# Serializer.net
KiCad netlist of a schematic drawn in Altium Designer
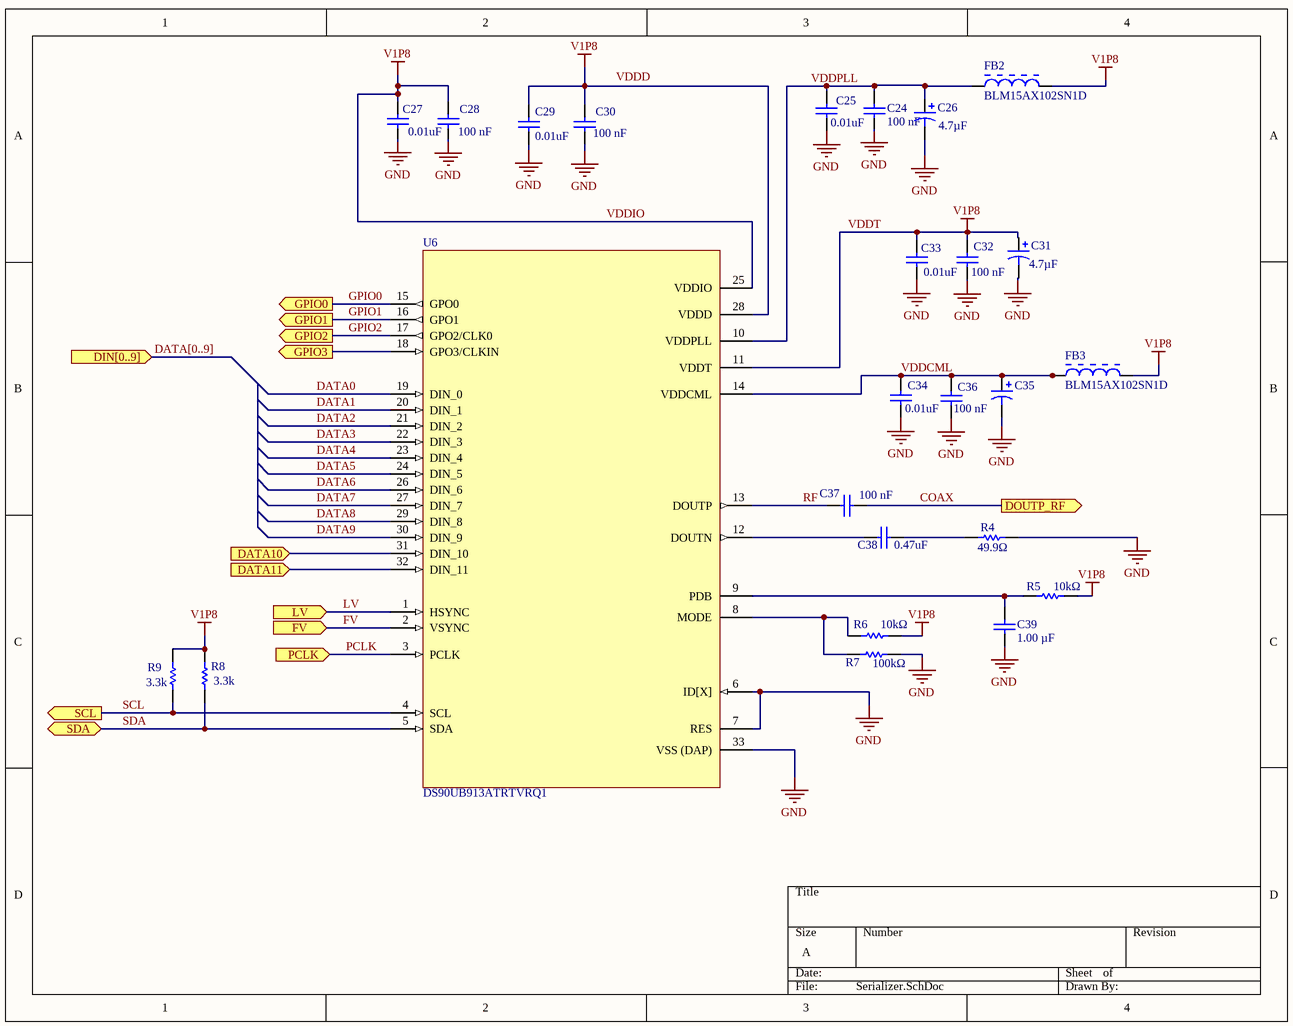
[diagram p0: Serializer.SchDoc]

(export (version "E")
  (design (tool "Eeschema 10.0.6"))
  (components
    (comp (ref "C24")
      (value "GRM033C71C104KE14D")
      (footprint "PCB-v6eq6etc9p7u7qdkgnno-1")
      (description "0.1 µF ±10% 16V Ceramic Capacitor X7S 0201 (0603 Metric)")
      (fields (field (name "CAPACITANCE") "100 nF"))
      (libsource (lib "Python_Imaging_1") (part "CMP-cc290632c88a13ee-3"))
    )
    (comp (ref "C25")
      (value "GRM033R71A103KA01D")
      (footprint "PCB-v6eq6etc9p7u7qdkgnno-1")
      (description "10000 pF ±10% 10V Ceramic Capacitor X7R 0201 (0603 Metric)")
      (fields (field (name "CAPACITANCE") "0.01uF"))
      (libsource (lib "Python_Imaging_1") (part "CMP-19299660-4"))
    )
    (comp (ref "C26")
      (value "F981A475MUALZT")
      (footprint "PCB-t0dwbiosd2m6unyihqym-1")
      (description "4.7 µF Molded Tantalum Capacitors 10 V 0402 (1005 Metric) -")
      (fields (field (name "CAPACITANCE") "4.7µF"))
      (libsource (lib "Python_Imaging_1") (part "SYM-b7737c8c1b6d68b4-1"))
    )
    (comp (ref "C27")
      (value "GRM033R71A103KA01D")
      (footprint "PCB-v6eq6etc9p7u7qdkgnno-1")
      (description "10000 pF ±10% 10V Ceramic Capacitor X7R 0201 (0603 Metric)")
      (fields (field (name "CAPACITANCE") "0.01uF"))
      (libsource (lib "Python_Imaging_1") (part "CMP-19299660-4"))
    )
    (comp (ref "C28")
      (value "GRM033C71C104KE14D")
      (footprint "PCB-v6eq6etc9p7u7qdkgnno-1")
      (description "0.1 µF ±10% 16V Ceramic Capacitor X7S 0201 (0603 Metric)")
      (fields (field (name "CAPACITANCE") "100 nF"))
      (libsource (lib "Python_Imaging_1") (part "CMP-cc290632c88a13ee-3"))
    )
    (comp (ref "C29")
      (value "GRM033R71A103KA01D")
      (footprint "PCB-v6eq6etc9p7u7qdkgnno-1")
      (description "10000 pF ±10% 10V Ceramic Capacitor X7R 0201 (0603 Metric)")
      (fields (field (name "CAPACITANCE") "0.01uF"))
      (libsource (lib "Python_Imaging_1") (part "CMP-19299660-4"))
    )
    (comp (ref "C30")
      (value "GRM033C71C104KE14D")
      (footprint "PCB-v6eq6etc9p7u7qdkgnno-1")
      (description "0.1 µF ±10% 16V Ceramic Capacitor X7S 0201 (0603 Metric)")
      (fields (field (name "CAPACITANCE") "100 nF"))
      (libsource (lib "Python_Imaging_1") (part "CMP-cc290632c88a13ee-3"))
    )
    (comp (ref "C31")
      (value "F981A475MUALZT")
      (footprint "PCB-t0dwbiosd2m6unyihqym-1")
      (description "4.7 µF Molded Tantalum Capacitors 10 V 0402 (1005 Metric) -")
      (fields (field (name "CAPACITANCE") "4.7µF"))
      (libsource (lib "Python_Imaging_1") (part "SYM-b7737c8c1b6d68b4-1"))
    )
    (comp (ref "C32")
      (value "GRM033C71C104KE14D")
      (footprint "PCB-v6eq6etc9p7u7qdkgnno-1")
      (description "0.1 µF ±10% 16V Ceramic Capacitor X7S 0201 (0603 Metric)")
      (fields (field (name "CAPACITANCE") "100 nF"))
      (libsource (lib "Python_Imaging_1") (part "CMP-cc290632c88a13ee-3"))
    )
    (comp (ref "C33")
      (value "GRM033R71A103KA01D")
      (footprint "PCB-v6eq6etc9p7u7qdkgnno-1")
      (description "10000 pF ±10% 10V Ceramic Capacitor X7R 0201 (0603 Metric)")
      (fields (field (name "CAPACITANCE") "0.01uF"))
      (libsource (lib "Python_Imaging_1") (part "CMP-19299660-4"))
    )
    (comp (ref "C34")
      (value "GRM033R71A103KA01D")
      (footprint "PCB-v6eq6etc9p7u7qdkgnno-1")
      (description "10000 pF ±10% 10V Ceramic Capacitor X7R 0201 (0603 Metric)")
      (fields (field (name "CAPACITANCE") "0.01uF"))
      (libsource (lib "Python_Imaging_1") (part "CMP-19299660-4"))
    )
    (comp (ref "C35")
      (value "F981A226MMALZT")
      (footprint "PCB-yxd74t6run51sg1ha7ug-1")
      (description "22 µF Molded Tantalum Capacitors 10 V 0603 (1608 Metric) 8Ohm @ 100kHz")
      (libsource (lib "Python_Imaging_1") (part "CMP-ed552659f9643292-2"))
    )
    (comp (ref "C36")
      (value "GRM033C71C104KE14D")
      (footprint "PCB-v6eq6etc9p7u7qdkgnno-1")
      (description "0.1 µF ±10% 16V Ceramic Capacitor X7S 0201 (0603 Metric)")
      (fields (field (name "CAPACITANCE") "100 nF"))
      (libsource (lib "Python_Imaging_1") (part "CMP-cc290632c88a13ee-3"))
    )
    (comp (ref "C37")
      (value "GRM033C71C104KE14D")
      (footprint "PCB-v6eq6etc9p7u7qdkgnno-1")
      (description "0.1 µF ±10% 16V Ceramic Capacitor X7S 0201 (0603 Metric)")
      (fields (field (name "CAPACITANCE") "100 nF"))
      (libsource (lib "Python_Imaging_1") (part "CMP-cc290632c88a13ee-3"))
    )
    (comp (ref "C38")
      (value "GRM033R60J473KE19D")
      (footprint "PCB-v6eq6etc9p7u7qdkgnno-1")
      (description "0.047 µF ±10% 6.3V Ceramic Capacitor X5R 0201 (0603 Metric)")
      (fields (field (name "CAPACITANCE") "0.47uF"))
      (libsource (lib "Python_Imaging_1") (part "CMP-131779-4"))
    )
    (comp (ref "C39")
      (value "GRM033R60J105MEA2D")
      (footprint "PCB-v6eq6etc9p7u7qdkgnno-1")
      (description "1 µF ±20% 6.3V Ceramic Capacitor X5R 0201 (0603 Metric)")
      (fields (field (name "CAPACITANCE") "1.00 µF"))
      (libsource (lib "Python_Imaging_1") (part "CMP-7dcab586fd61a20d-5"))
    )
    (comp (ref "FB2")
      (value "BLM15AX102SN1D")
      (footprint "MURA-BLM15-CHIP-2_V")
      (description "1 kOhms @ 100 MHz 1 - Ferrite Bead 0402 (1005 Metric) 350mA 490mOhm")
      (libsource (lib "Python_Imaging_1") (part "MURA-FB-2"))
    )
    (comp (ref "FB3")
      (value "BLM15AX102SN1D")
      (footprint "MURA-BLM15-CHIP-2_V")
      (description "1 kOhms @ 100 MHz 1 - Ferrite Bead 0402 (1005 Metric) 350mA 490mOhm")
      (libsource (lib "Python_Imaging_1") (part "MURA-FB-2"))
    )
    (comp (ref "R4")
      (value "TNPW020149R9BEED")
      (footprint "PCB-7g93mzch2qc2q3jid3ok-1")
      (fields (field (name "RESISTANCE") "49.9Ω"))
      (libsource (lib "Python_Imaging_1") (part "CMP-1848375-4"))
    )
    (comp (ref "R5")
      (value "ERJ-1GNF1002C")
      (footprint "PCB-7g93mzch2qc2q3jid3ok-1")
      (description "10 kOhms ±1% 0.05W, 1/20W Chip Resistor 0201 (0603 Metric) Automotive AEC-Q200 Thick Film")
      (fields (field (name "RESISTANCE") "10kΩ"))
      (libsource (lib "Python_Imaging_1") (part "CMP-1848298-4"))
    )
    (comp (ref "R6")
      (value "ERJ-1GNF1002C")
      (footprint "PCB-7g93mzch2qc2q3jid3ok-1")
      (description "10 kOhms ±1% 0.05W, 1/20W Chip Resistor 0201 (0603 Metric) Automotive AEC-Q200 Thick Film")
      (fields (field (name "RESISTANCE") "10kΩ"))
      (libsource (lib "Python_Imaging_1") (part "CMP-1848298-4"))
    )
    (comp (ref "R7")
      (value "ERJ-1GNF1003C")
      (footprint "PCB-7g93mzch2qc2q3jid3ok-1")
      (description "100 kOhms ±1% 0.05W, 1/20W Chip Resistor 0201 (0603 Metric) Automotive AEC-Q200 Thick Film")
      (fields (field (name "RESISTANCE") "100kΩ"))
      (libsource (lib "Python_Imaging_1") (part "CMP-1848300-4"))
    )
    (comp (ref "R8")
      (value "ERJ-1GNF3301C")
      (footprint "PCB-7g93mzch2qc2q3jid3ok-1")
      (description "3.3 kOhms ±1% 0.05W, 1/20W Chip Resistor 0201 (0603 Metric) Automotive AEC-Q200 Thick Film")
      (fields (field (name "RESISTANCE") "3.3k"))
      (libsource (lib "Python_Imaging_1") (part "CMP-1848326-4"))
    )
    (comp (ref "R9")
      (value "ERJ-1GNF3301C")
      (footprint "PCB-7g93mzch2qc2q3jid3ok-1")
      (description "3.3 kOhms ±1% 0.05W, 1/20W Chip Resistor 0201 (0603 Metric) Automotive AEC-Q200 Thick Film")
      (fields (field (name "RESISTANCE") "3.3k"))
      (libsource (lib "Python_Imaging_1") (part "CMP-1848326-4"))
    )
    (comp (ref "U6")
      (value "DS90UB913ATRTVRQ1")
      (footprint "PCB-l2nnig1h4ckv44w98gav-1")
      (description "1.4Gbps Serializer 12 Input 1 Output 32-WQFN (5x5)")
      (libsource (lib "Python_Imaging_1") (part "CMP-1f96d75fdae3c051-6"))
    )
  )
  (nets
    (net (code "1") (name "/COAX") (class "Default")
      (node (ref "C37") (pin "1") (pinfunction "1_1") (pintype "passive"))
    )
    (net (code "2") (name "/DATA0") (class "Default")
      (node (ref "U6") (pin "19") (pinfunction "DIN_0_19") (pintype "input"))
    )
    (net (code "3") (name "/DATA1") (class "Default")
      (node (ref "U6") (pin "20") (pinfunction "DIN_1_20") (pintype "input"))
    )
    (net (code "4") (name "/DATA2") (class "Default")
      (node (ref "U6") (pin "21") (pinfunction "DIN_2_21") (pintype "input"))
    )
    (net (code "5") (name "/DATA3") (class "Default")
      (node (ref "U6") (pin "22") (pinfunction "DIN_3_22") (pintype "input"))
    )
    (net (code "6") (name "/DATA4") (class "Default")
      (node (ref "U6") (pin "23") (pinfunction "DIN_4_23") (pintype "input"))
    )
    (net (code "7") (name "/DATA5") (class "Default")
      (node (ref "U6") (pin "24") (pinfunction "DIN_5_24") (pintype "input"))
    )
    (net (code "8") (name "/DATA6") (class "Default")
      (node (ref "U6") (pin "26") (pinfunction "DIN_6_26") (pintype "input"))
    )
    (net (code "9") (name "/DATA7") (class "Default")
      (node (ref "U6") (pin "27") (pinfunction "DIN_7_27") (pintype "input"))
    )
    (net (code "10") (name "/DATA8") (class "Default")
      (node (ref "U6") (pin "29") (pinfunction "DIN_8_29") (pintype "input"))
    )
    (net (code "11") (name "/DATA9") (class "Default")
      (node (ref "U6") (pin "30") (pinfunction "DIN_9_30") (pintype "input"))
    )
    (net (code "12") (name "/DATA10") (class "Default")
      (node (ref "U6") (pin "31") (pinfunction "DIN_10_31") (pintype "input"))
    )
    (net (code "13") (name "/DATA11") (class "Default")
      (node (ref "U6") (pin "32") (pinfunction "DIN_11_32") (pintype "input"))
    )
    (net (code "15") (name "/FV") (class "Default")
      (node (ref "U6") (pin "2") (pinfunction "VSYNC_2") (pintype "input"))
    )
    (net (code "16") (name "/GPIO0") (class "Default")
      (node (ref "U6") (pin "15") (pinfunction "GPO0_15") (pintype "output"))
    )
    (net (code "17") (name "/GPIO1") (class "Default")
      (node (ref "U6") (pin "16") (pinfunction "GPO1_16") (pintype "output"))
    )
    (net (code "18") (name "/GPIO2") (class "Default")
      (node (ref "U6") (pin "17") (pinfunction "GPO2/CLK0_17") (pintype "output"))
    )
    (net (code "19") (name "/GPIO3") (class "Default")
      (node (ref "U6") (pin "18") (pinfunction "GPO3/CLKIN_18") (pintype "input"))
    )
    (net (code "20") (name "/LV") (class "Default")
      (node (ref "U6") (pin "1") (pinfunction "HSYNC_1") (pintype "input"))
    )
    (net (code "21") (name "/PCLK") (class "Default")
      (node (ref "U6") (pin "3") (pinfunction "PCLK_3") (pintype "input"))
    )
    (net (code "22") (name "/RF") (class "Default")
      (node (ref "C37") (pin "2") (pinfunction "2_2") (pintype "passive"))
      (node (ref "U6") (pin "13") (pinfunction "DOUTP_13") (pintype "output"))
    )
    (net (code "23") (name "/SCL") (class "Default")
      (node (ref "R9") (pin "1") (pinfunction "1_1") (pintype "passive"))
      (node (ref "U6") (pin "4") (pinfunction "SCL_4") (pintype "input"))
    )
    (net (code "24") (name "/SDA") (class "Default")
      (node (ref "R8") (pin "1") (pinfunction "1_1") (pintype "passive"))
      (node (ref "U6") (pin "5") (pinfunction "SDA_5") (pintype "input"))
    )
    (net (code "25") (name "/VDDCML") (class "Default")
      (node (ref "C34") (pin "2") (pinfunction "2_2") (pintype "passive"))
      (node (ref "C35") (pin "1") (pinfunction "1_1") (pintype "passive"))
      (node (ref "C36") (pin "2") (pinfunction "2_2") (pintype "passive"))
      (node (ref "FB3") (pin "1") (pinfunction "1_1") (pintype "passive"))
      (node (ref "U6") (pin "14") (pinfunction "VDDCML_14") (pintype "power_in"))
    )
    (net (code "27") (name "/VDDPLL") (class "Default")
      (node (ref "C24") (pin "2") (pinfunction "2_2") (pintype "passive"))
      (node (ref "C25") (pin "2") (pinfunction "2_2") (pintype "passive"))
      (node (ref "C26") (pin "1") (pinfunction "1_1") (pintype "passive"))
      (node (ref "FB2") (pin "1") (pinfunction "1_1") (pintype "passive"))
      (node (ref "U6") (pin "10") (pinfunction "VDDPLL_10") (pintype "power_in"))
    )
    (net (code "28") (name "GND") (class "Default")
      (node (ref "C24") (pin "1") (pinfunction "1_1") (pintype "passive"))
      (node (ref "C25") (pin "1") (pinfunction "1_1") (pintype "passive"))
      (node (ref "C26") (pin "2") (pinfunction "2_2") (pintype "passive"))
      (node (ref "C27") (pin "1") (pinfunction "1_1") (pintype "passive"))
      (node (ref "C28") (pin "1") (pinfunction "1_1") (pintype "passive"))
      (node (ref "C29") (pin "1") (pinfunction "1_1") (pintype "passive"))
      (node (ref "C30") (pin "1") (pinfunction "1_1") (pintype "passive"))
      (node (ref "C31") (pin "2") (pinfunction "2_2") (pintype "passive"))
      (node (ref "C32") (pin "1") (pinfunction "1_1") (pintype "passive"))
      (node (ref "C33") (pin "1") (pinfunction "1_1") (pintype "passive"))
      (node (ref "C34") (pin "1") (pinfunction "1_1") (pintype "passive"))
      (node (ref "C35") (pin "2") (pinfunction "2_2") (pintype "passive"))
      (node (ref "C36") (pin "1") (pinfunction "1_1") (pintype "passive"))
      (node (ref "C39") (pin "1") (pinfunction "1_1") (pintype "passive"))
      (node (ref "R4") (pin "2") (pinfunction "2_2") (pintype "passive"))
      (node (ref "R7") (pin "2") (pinfunction "2_2") (pintype "passive"))
      (node (ref "U6") (pin "33") (pinfunction "VSS_(DAP)_33") (pintype "power_in"))
      (node (ref "U6") (pin "6") (pinfunction "ID[X]_6") (pintype "input"))
      (node (ref "U6") (pin "7") (pinfunction "RES_7") (pintype "power_in"))
    )
    (net (code "29") (name "Net-(C38-Pad2)") (class "Default")
      (node (ref "C38") (pin "2") (pinfunction "2_2") (pintype "passive"))
      (node (ref "R4") (pin "1") (pinfunction "1_1") (pintype "passive"))
    )
    (net (code "30") (name "Net-(U6-DOUTN)") (class "Default")
      (node (ref "C38") (pin "1") (pinfunction "1_1") (pintype "passive"))
      (node (ref "U6") (pin "12") (pinfunction "DOUTN_12") (pintype "output"))
    )
    (net (code "31") (name "Net-(U6-MODE)") (class "Default")
      (node (ref "R6") (pin "1") (pinfunction "1_1") (pintype "passive"))
      (node (ref "R7") (pin "1") (pinfunction "1_1") (pintype "passive"))
      (node (ref "U6") (pin "8") (pinfunction "MODE_8") (pintype "passive"))
    )
    (net (code "32") (name "Net-(U6-PDB)") (class "Default")
      (node (ref "C39") (pin "2") (pinfunction "2_2") (pintype "passive"))
      (node (ref "R5") (pin "1") (pinfunction "1_1") (pintype "passive"))
      (node (ref "U6") (pin "9") (pinfunction "PDB_9") (pintype "passive"))
    )
    (net (code "33") (name "V1P8") (class "Default")
      (node (ref "C27") (pin "2") (pinfunction "2_2") (pintype "passive"))
      (node (ref "C28") (pin "2") (pinfunction "2_2") (pintype "passive"))
      (node (ref "C29") (pin "2") (pinfunction "2_2") (pintype "passive"))
      (node (ref "C30") (pin "2") (pinfunction "2_2") (pintype "passive"))
      (node (ref "C31") (pin "1") (pinfunction "1_1") (pintype "passive"))
      (node (ref "C32") (pin "2") (pinfunction "2_2") (pintype "passive"))
      (node (ref "C33") (pin "2") (pinfunction "2_2") (pintype "passive"))
      (node (ref "FB2") (pin "2") (pinfunction "2_2") (pintype "passive"))
      (node (ref "FB3") (pin "2") (pinfunction "2_2") (pintype "passive"))
      (node (ref "R5") (pin "2") (pinfunction "2_2") (pintype "passive"))
      (node (ref "R6") (pin "2") (pinfunction "2_2") (pintype "passive"))
      (node (ref "R8") (pin "2") (pinfunction "2_2") (pintype "passive"))
      (node (ref "R9") (pin "2") (pinfunction "2_2") (pintype "passive"))
      (node (ref "U6") (pin "11") (pinfunction "VDDT_11") (pintype "power_in"))
      (node (ref "U6") (pin "25") (pinfunction "VDDIO_25") (pintype "power_in"))
      (node (ref "U6") (pin "28") (pinfunction "VDDD_28") (pintype "power_in"))
    )
  )
)
